# seismometer_sensormodule.net
KiCad netlist of a schematic drawn in EAGLE
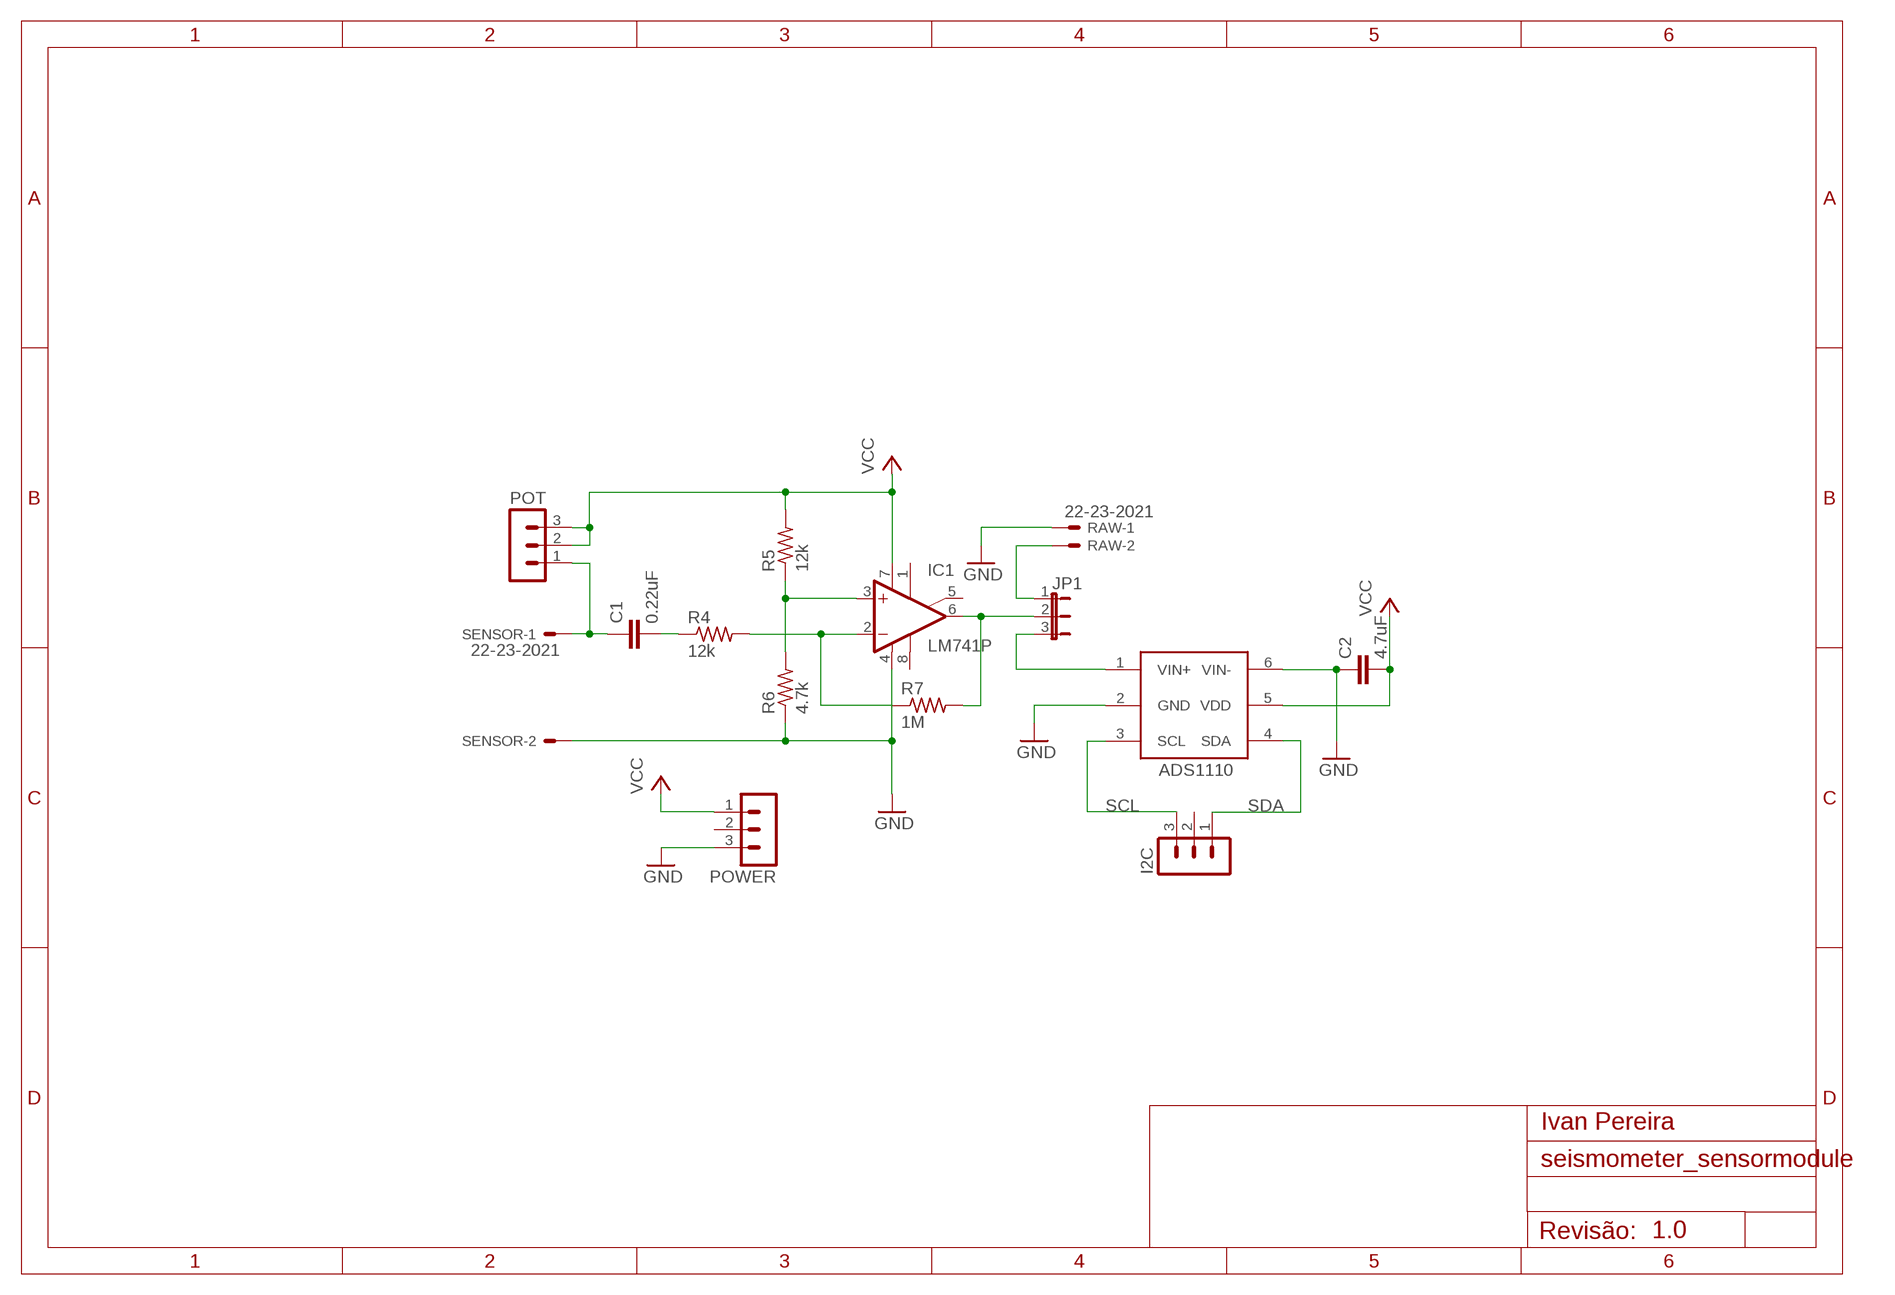
[diagram p0: schematic, sheet 1]

(export (version "E")
  (design (tool "Eeschema 10.0.6"))
  (components
    (comp (ref "C1")
      (value "0.22uF")
      (footprint "eagle-import:C025-030X050")
      (libsource (lib "eagle-import") (part "C-EU025-030X050"))
    )
    (comp (ref "C2")
      (value "4.7uF")
      (footprint "eagle-import:C025-030X050")
      (libsource (lib "eagle-import") (part "C-EU025-030X050"))
    )
    (comp (ref "I2C")
      (value "MA03-1")
      (footprint "eagle-import:MA03-1")
      (libsource (lib "eagle-import") (part "MA03-1"))
    )
    (comp (ref "IC1")
      (value "LM741P")
      (footprint "eagle-import:DIL08")
      (libsource (lib "eagle-import") (part "741PLM"))
    )
    (comp (ref "IC2")
      (value "ADS1110")
      (footprint "eagle-import:SOT-23-6")
      (libsource (lib "eagle-import") (part "ADS1110"))
    )
    (comp (ref "JP1")
      (value "JP2E")
      (footprint "eagle-import:JP2")
      (libsource (lib "eagle-import") (part "JP2E"))
    )
    (comp (ref "POT")
      (value "MA03-1")
      (footprint "eagle-import:MA03-1")
      (libsource (lib "eagle-import") (part "MA03-1"))
    )
    (comp (ref "POWER")
      (value "MA03-1")
      (footprint "eagle-import:MA03-1")
      (libsource (lib "eagle-import") (part "MA03-1"))
    )
    (comp (ref "R4")
      (value "12k")
      (footprint "eagle-import:0207_12")
      (libsource (lib "eagle-import") (part "R-US_0207/12"))
    )
    (comp (ref "R5")
      (value "12k")
      (footprint "eagle-import:0207_12")
      (libsource (lib "eagle-import") (part "R-US_0207/12"))
    )
    (comp (ref "R6")
      (value "4.7k")
      (footprint "eagle-import:0207_12")
      (libsource (lib "eagle-import") (part "R-US_0207/12"))
    )
    (comp (ref "R7")
      (value "1M")
      (footprint "eagle-import:0207_12")
      (libsource (lib "eagle-import") (part "R-US_0207/12"))
    )
    (comp (ref "RAW")
      (value "22-23-2021")
      (footprint "eagle-import:22-23-2021")
      (fields (field (name "MF") "MOLEX"))
      (libsource (lib "eagle-import") (part "22-23-2021"))
    )
    (comp (ref "SENSOR")
      (value "22-23-2021")
      (footprint "eagle-import:22-23-2021")
      (fields (field (name "MF") "MOLEX"))
      (libsource (lib "eagle-import") (part "22-23-2021"))
    )
  )
  (nets
    (net (code "1") (name "/SCL") (class "Default")
      (node (ref "I2C") (pin "3") (pinfunction "3_3") (pintype "passive"))
      (node (ref "IC2") (pin "3") (pinfunction "SCL_3") (pintype "bidirectional"))
    )
    (net (code "2") (name "/SDA") (class "Default")
      (node (ref "I2C") (pin "1") (pinfunction "1_1") (pintype "passive"))
      (node (ref "IC2") (pin "4") (pinfunction "SDA_4") (pintype "bidirectional"))
    )
    (net (code "3") (name "GND") (class "Default")
      (node (ref "C2") (pin "1") (pinfunction "1_1") (pintype "passive"))
      (node (ref "IC1") (pin "4") (pinfunction "V-_4") (pintype "power_in"))
      (node (ref "IC2") (pin "2") (pinfunction "GND_2") (pintype "bidirectional"))
      (node (ref "IC2") (pin "6") (pinfunction "VIN-_6") (pintype "bidirectional"))
      (node (ref "POWER") (pin "3") (pinfunction "3_3") (pintype "passive"))
      (node (ref "R6") (pin "1") (pinfunction "1_1") (pintype "passive"))
      (node (ref "RAW") (pin "1") (pinfunction "S_1") (pintype "passive"))
      (node (ref "SENSOR") (pin "2") (pinfunction "S_2") (pintype "passive"))
    )
    (net (code "4") (name "Net-(C1-Pad2)") (class "Default")
      (node (ref "C1") (pin "2") (pinfunction "2_2") (pintype "passive"))
      (node (ref "R4") (pin "1") (pinfunction "1_1") (pintype "passive"))
    )
    (net (code "5") (name "Net-(IC1-+IN)") (class "Default")
      (node (ref "IC1") (pin "3") (pinfunction "+IN_3") (pintype "input"))
      (node (ref "R5") (pin "1") (pinfunction "1_1") (pintype "passive"))
      (node (ref "R6") (pin "2") (pinfunction "2_2") (pintype "passive"))
    )
    (net (code "6") (name "Net-(IC1--IN)") (class "Default")
      (node (ref "IC1") (pin "2") (pinfunction "-IN_2") (pintype "input"))
      (node (ref "R4") (pin "2") (pinfunction "2_2") (pintype "passive"))
      (node (ref "R7") (pin "1") (pinfunction "1_1") (pintype "passive"))
    )
    (net (code "7") (name "Net-(IC1-OUT)") (class "Default")
      (node (ref "IC1") (pin "6") (pinfunction "OUT_6") (pintype "output"))
      (node (ref "JP1") (pin "2") (pinfunction "2_2") (pintype "passive"))
      (node (ref "R7") (pin "2") (pinfunction "2_2") (pintype "passive"))
    )
    (net (code "8") (name "Net-(IC2-VIN+)") (class "Default")
      (node (ref "IC2") (pin "1") (pinfunction "VIN+_1") (pintype "bidirectional"))
      (node (ref "JP1") (pin "3") (pinfunction "3_3") (pintype "passive"))
    )
    (net (code "9") (name "Net-(RAWB-S)") (class "Default")
      (node (ref "JP1") (pin "1") (pinfunction "1_1") (pintype "passive"))
      (node (ref "RAW") (pin "2") (pinfunction "S_2") (pintype "passive"))
    )
    (net (code "10") (name "Net-(SENSORA-S)") (class "Default")
      (node (ref "C1") (pin "1") (pinfunction "1_1") (pintype "passive"))
      (node (ref "POT") (pin "1") (pinfunction "1_1") (pintype "passive"))
      (node (ref "SENSOR") (pin "1") (pinfunction "S_1") (pintype "passive"))
    )
    (net (code "11") (name "VCC") (class "Default")
      (node (ref "C2") (pin "2") (pinfunction "2_2") (pintype "passive"))
      (node (ref "IC1") (pin "7") (pinfunction "V+_7") (pintype "power_in"))
      (node (ref "IC2") (pin "5") (pinfunction "VDD_5") (pintype "bidirectional"))
      (node (ref "POT") (pin "2") (pinfunction "2_2") (pintype "passive"))
      (node (ref "POT") (pin "3") (pinfunction "3_3") (pintype "passive"))
      (node (ref "POWER") (pin "1") (pinfunction "1_1") (pintype "passive"))
      (node (ref "R5") (pin "2") (pinfunction "2_2") (pintype "passive"))
    )
    (net (code "12") (name "unconnected-(I2C-Pad2)") (class "Default")
      (node (ref "I2C") (pin "2") (pinfunction "2_2") (pintype "passive"))
    )
    (net (code "13") (name "unconnected-(IC1-ON1-Pad1)") (class "Default")
      (node (ref "IC1") (pin "1") (pinfunction "ON1_1") (pintype "passive"))
    )
    (net (code "14") (name "unconnected-(IC1-ON2-Pad5)") (class "Default")
      (node (ref "IC1") (pin "5") (pinfunction "ON2_5") (pintype "passive"))
    )
    (net (code "15") (name "unconnected-(IC1-OPT-Pad8)") (class "Default")
      (node (ref "IC1") (pin "8") (pinfunction "OPT_8") (pintype "passive"))
    )
    (net (code "16") (name "unconnected-(POWER-Pad2)") (class "Default")
      (node (ref "POWER") (pin "2") (pinfunction "2_2") (pintype "passive"))
    )
  )
)
